# lampka.net
KiCad netlist of a schematic drawn in EAGLE
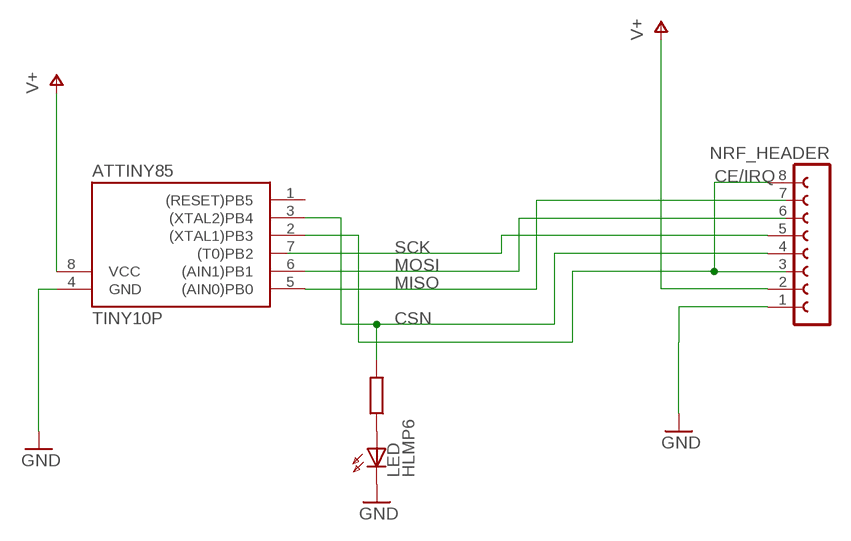
[diagram p0: schematic, sheet 1]

(export (version "E")
  (design (tool "Eeschema 10.0.6"))
  (components
    (comp (ref "ATTINY85")
      (value "TINY10P")
      (footprint "eagle-import:DIL08")
      (libsource (lib "eagle-import") (part "TINY10P"))
    )
    (comp (ref "LED")
      (value "HLMP6")
      (footprint "eagle-import:HLMP6")
      (fields (field (name "MF") "AGILENT TECHNOLOGIES") (field (name "MPN") "HLMP-6500"))
      (libsource (lib "eagle-import") (part "HLMP6"))
    )
    (comp (ref "NRF_HEADER")
      (value "FE08-1")
      (footprint "eagle-import:FE08")
      (libsource (lib "eagle-import") (part "FE08-1"))
    )
  )
  (nets
    (net (code "1") (name "/CE{slash}IRQ") (class "Default")
      (node (ref "ATTINY85") (pin "2") (pinfunction "(XTAL1)PB3_2") (pintype "bidirectional"))
      (node (ref "NRF_HEADER") (pin "8") (pinfunction "8_8") (pintype "passive"))
    )
    (net (code "2") (name "/CSN") (class "Default")
      (node (ref "ATTINY85") (pin "3") (pinfunction "(XTAL2)PB4_3") (pintype "bidirectional"))
      (node (ref "NRF_HEADER") (pin "4") (pinfunction "4_4") (pintype "passive"))
    )
    (net (code "3") (name "/MISO") (class "Default")
      (node (ref "ATTINY85") (pin "5") (pinfunction "(AIN0)PB0_5") (pintype "bidirectional"))
    )
    (net (code "4") (name "/MOSI") (class "Default")
      (node (ref "ATTINY85") (pin "6") (pinfunction "(AIN1)PB1_6") (pintype "bidirectional"))
    )
    (net (code "5") (name "/SCK") (class "Default")
      (node (ref "NRF_HEADER") (pin "5") (pinfunction "5_5") (pintype "passive"))
    )
    (net (code "6") (name "GND") (class "Default")
      (node (ref "ATTINY85") (pin "4") (pinfunction "GND_4") (pintype "power_in"))
      (node (ref "LED") (pin "K") (pinfunction "K_K") (pintype "passive"))
      (node (ref "NRF_HEADER") (pin "1") (pinfunction "1_1") (pintype "passive"))
    )
    (net (code "7") (name "V+") (class "Default")
      (node (ref "ATTINY85") (pin "8") (pinfunction "VCC_8") (pintype "power_in"))
      (node (ref "NRF_HEADER") (pin "2") (pinfunction "2_2") (pintype "passive"))
    )
    (net (code "8") (name "unconnected-(ATTINY85-(RESET)PB5-Pad1)") (class "Default")
      (node (ref "ATTINY85") (pin "1") (pinfunction "(RESET)PB5_1") (pintype "bidirectional"))
    )
    (net (code "9") (name "unconnected-(ATTINY85-(T0)PB2-Pad7)") (class "Default")
      (node (ref "ATTINY85") (pin "7") (pinfunction "(T0)PB2_7") (pintype "bidirectional"))
    )
    (net (code "10") (name "unconnected-(LED-PadA)") (class "Default")
      (node (ref "LED") (pin "A") (pinfunction "A_A") (pintype "passive"))
    )
    (net (code "11") (name "unconnected-(NRF_HEADER-Pad3)") (class "Default")
      (node (ref "NRF_HEADER") (pin "3") (pinfunction "3_3") (pintype "passive"))
    )
    (net (code "12") (name "unconnected-(NRF_HEADER-Pad6)") (class "Default")
      (node (ref "NRF_HEADER") (pin "6") (pinfunction "6_6") (pintype "passive"))
    )
    (net (code "13") (name "unconnected-(NRF_HEADER-Pad7)") (class "Default")
      (node (ref "NRF_HEADER") (pin "7") (pinfunction "7_7") (pintype "passive"))
    )
  )
)
